# GG-CC1101_v1.net
KiCad netlist of a schematic drawn in EAGLE
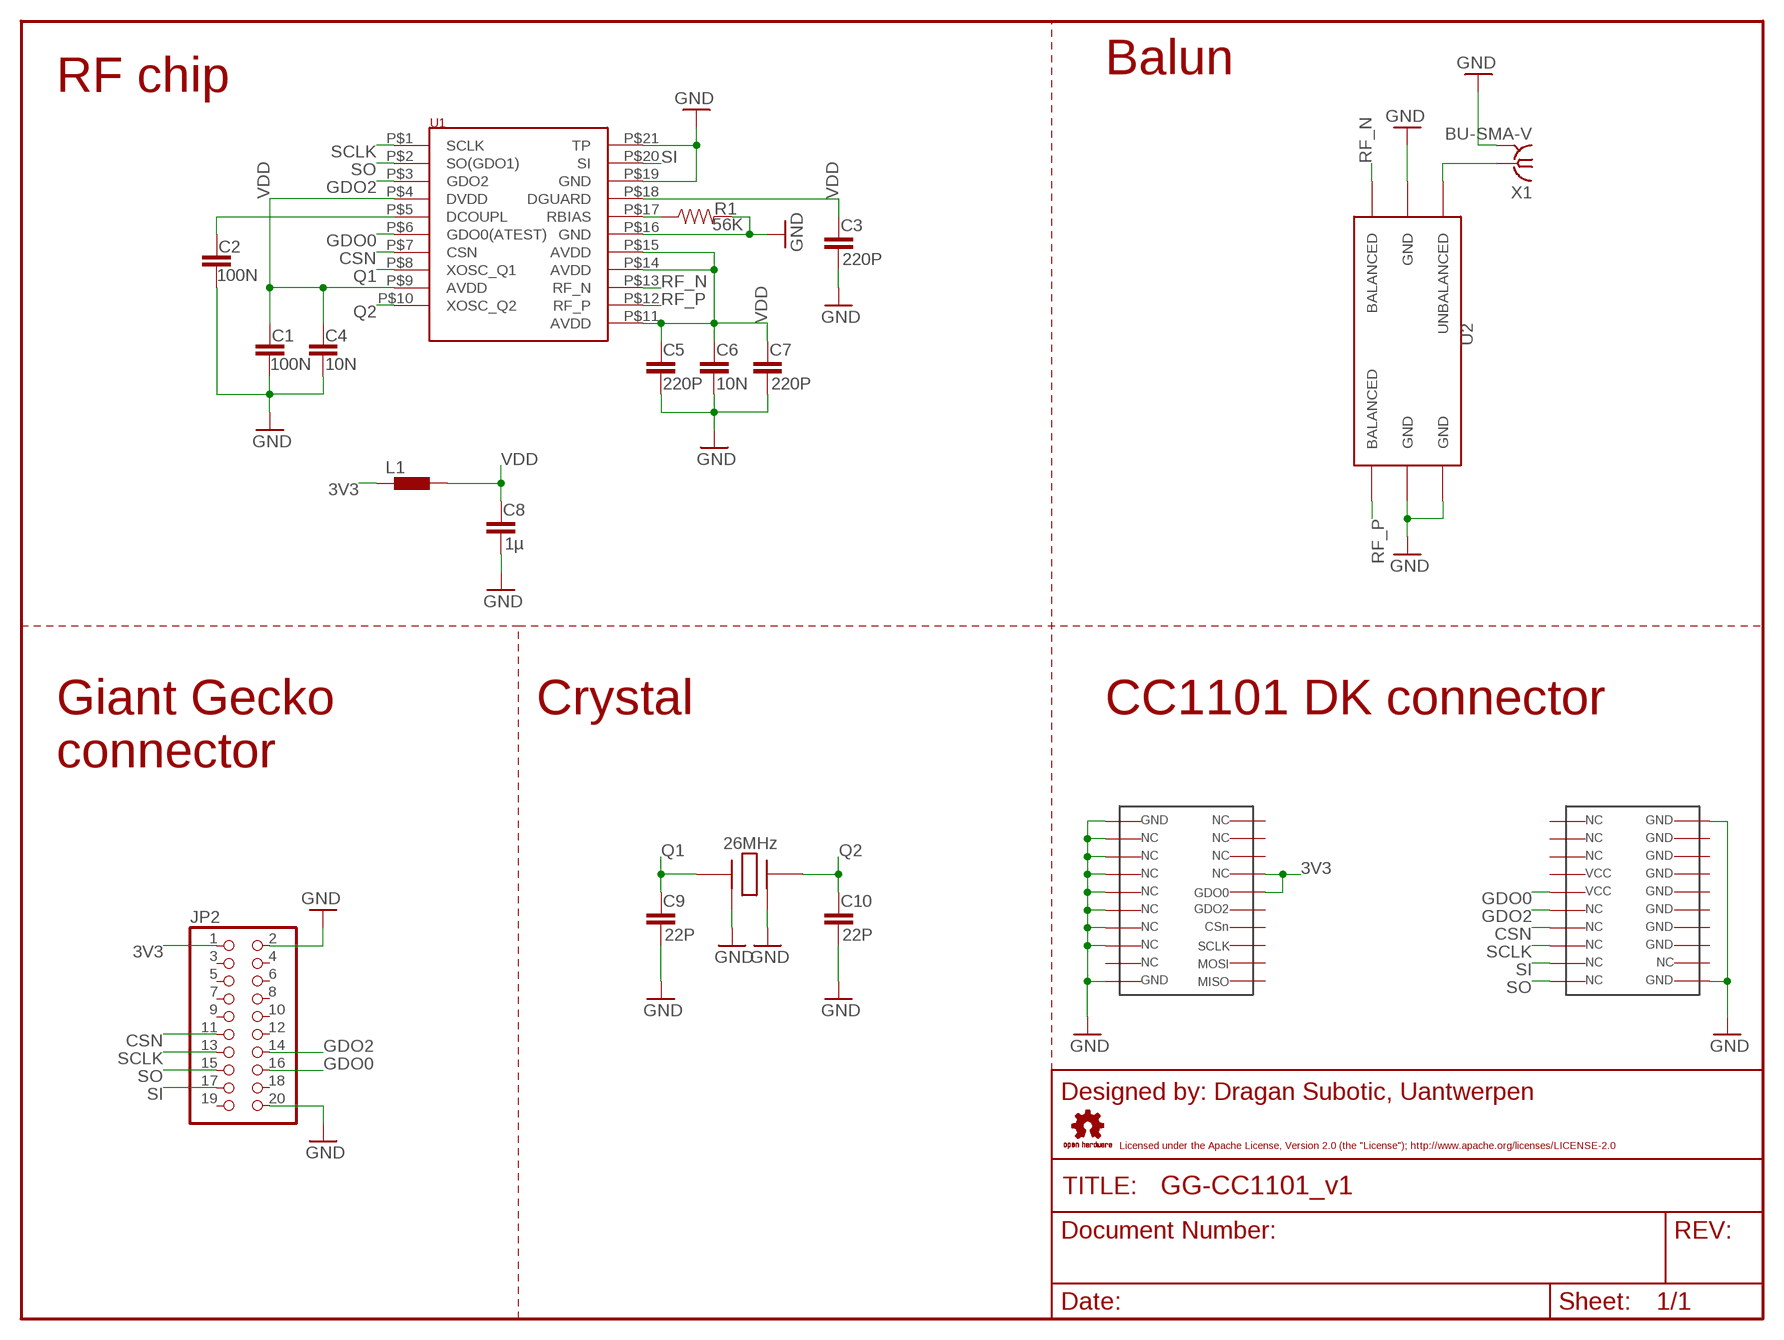
[diagram p0: schematic, sheet 1]

(export (version "E")
  (design (tool "Eeschema 10.0.6"))
  (components
    (comp (ref "C1")
      (value "100N")
      (footprint "eagle-import:0805")
      (libsource (lib "eagle-import") (part "CAP0805"))
    )
    (comp (ref "C2")
      (value "100N")
      (footprint "eagle-import:0805")
      (libsource (lib "eagle-import") (part "CAP0805"))
    )
    (comp (ref "C3")
      (value "220P")
      (footprint "eagle-import:0805")
      (libsource (lib "eagle-import") (part "CAP0805"))
    )
    (comp (ref "C4")
      (value "10N")
      (footprint "eagle-import:0805")
      (libsource (lib "eagle-import") (part "CAP0805"))
    )
    (comp (ref "C5")
      (value "220P")
      (footprint "eagle-import:0805")
      (libsource (lib "eagle-import") (part "CAP0805"))
    )
    (comp (ref "C6")
      (value "10N")
      (footprint "eagle-import:0805")
      (libsource (lib "eagle-import") (part "CAP0805"))
    )
    (comp (ref "C7")
      (value "220P")
      (footprint "eagle-import:0805")
      (libsource (lib "eagle-import") (part "CAP0805"))
    )
    (comp (ref "C8")
      (value "1µ")
      (footprint "eagle-import:0805")
      (libsource (lib "eagle-import") (part "CAP0805"))
    )
    (comp (ref "C9")
      (value "22P")
      (footprint "eagle-import:0805")
      (libsource (lib "eagle-import") (part "CAP0805"))
    )
    (comp (ref "C10")
      (value "22P")
      (footprint "eagle-import:0805")
      (libsource (lib "eagle-import") (part "CAP0805"))
    )
    (comp (ref "JP2")
      (value "PINHD-2X10")
      (footprint "eagle-import:2X10")
      (libsource (lib "eagle-import") (part "PINHD-2X10"))
    )
    (comp (ref "L1")
      (value "BLM15HG102SN1")
      (footprint "eagle-import:0402")
      (libsource (lib "eagle-import") (part "BLM15HG102SN1"))
    )
    (comp (ref "R1")
      (value "56K")
      (footprint "eagle-import:0805")
      (libsource (lib "eagle-import") (part "RESISTOR0805-RES"))
    )
    (comp (ref "U$1")
      (value "CC1101-EVAL_KIT")
      (footprint "eagle-import:CC1101-EVAL_KIT")
      (libsource (lib "eagle-import") (part "CC1101-EVAL_KIT"))
    )
    (comp (ref "U$2")
      (value "XTAL-26MHZ")
      (footprint "eagle-import:XTAL-26MHZ")
      (libsource (lib "eagle-import") (part "XTAL-26MHZ"))
    )
    (comp (ref "U1")
      (value "CC1101")
      (footprint "eagle-import:CC1101")
      (libsource (lib "eagle-import") (part "CC1101"))
    )
    (comp (ref "U2")
      (value "BALUN-433MHZ")
      (footprint "eagle-import:BALUN-433MHZ")
      (libsource (lib "eagle-import") (part "BALUN-433MHZ"))
    )
    (comp (ref "X1")
      (value "BU-SMA-V")
      (footprint "eagle-import:BU-SMA-V")
      (libsource (lib "eagle-import") (part "BU-SMA-V"))
    )
  )
  (nets
    (net (code "1") (name "/3V3") (class "Default")
      (node (ref "JP2") (pin "1") (pinfunction "1_1") (pintype "passive"))
      (node (ref "L1") (pin "1") (pinfunction "1_1") (pintype "passive"))
      (node (ref "U$1") (pin "P$14") (pinfunction "P$14_P$14") (pintype "bidirectional"))
      (node (ref "U$1") (pin "P$15") (pinfunction "P$15_P$15") (pintype "bidirectional"))
    )
    (net (code "2") (name "/CSN") (class "Default")
      (node (ref "JP2") (pin "11") (pinfunction "11_11") (pintype "passive"))
      (node (ref "U$1") (pin "P$24") (pinfunction "P$24_P$24") (pintype "bidirectional"))
      (node (ref "U1") (pin "P$7") (pinfunction "CSN_P$7") (pintype "bidirectional"))
    )
    (net (code "3") (name "/GDO0") (class "Default")
      (node (ref "JP2") (pin "16") (pinfunction "16_16") (pintype "passive"))
      (node (ref "U$1") (pin "P$26") (pinfunction "P$26_P$26") (pintype "bidirectional"))
      (node (ref "U1") (pin "P$6") (pinfunction "GDO0(ATEST)_P$6") (pintype "bidirectional"))
    )
    (net (code "4") (name "/GDO2") (class "Default")
      (node (ref "JP2") (pin "14") (pinfunction "14_14") (pintype "passive"))
      (node (ref "U$1") (pin "P$25") (pinfunction "P$25_P$25") (pintype "bidirectional"))
      (node (ref "U1") (pin "P$3") (pinfunction "GDO2_P$3") (pintype "bidirectional"))
    )
    (net (code "5") (name "/Q1") (class "Default")
      (node (ref "C9") (pin "1") (pinfunction "1_1") (pintype "passive"))
      (node (ref "U$2") (pin "P$1") (pinfunction "P$1_P$1") (pintype "bidirectional"))
      (node (ref "U1") (pin "P$8") (pinfunction "XOSC_Q1_P$8") (pintype "bidirectional"))
    )
    (net (code "6") (name "/Q2") (class "Default")
      (node (ref "C10") (pin "1") (pinfunction "1_1") (pintype "passive"))
      (node (ref "U$2") (pin "P$3") (pinfunction "P$3_P$3") (pintype "bidirectional"))
      (node (ref "U1") (pin "P$10") (pinfunction "XOSC_Q2_P$10") (pintype "bidirectional"))
    )
    (net (code "7") (name "/RF_N") (class "Default")
      (node (ref "U1") (pin "P$13") (pinfunction "RF_N_P$13") (pintype "bidirectional"))
      (node (ref "U2") (pin "P$3") (pinfunction "BALANCED_P$3") (pintype "bidirectional"))
    )
    (net (code "8") (name "/RF_P") (class "Default")
      (node (ref "U1") (pin "P$12") (pinfunction "RF_P_P$12") (pintype "bidirectional"))
      (node (ref "U2") (pin "P$4") (pinfunction "BALANCED_P$4") (pintype "bidirectional"))
    )
    (net (code "9") (name "/SCLK") (class "Default")
      (node (ref "JP2") (pin "13") (pinfunction "13_13") (pintype "passive"))
      (node (ref "U$1") (pin "P$23") (pinfunction "P$23_P$23") (pintype "bidirectional"))
      (node (ref "U1") (pin "P$1") (pinfunction "SCLK_P$1") (pintype "bidirectional"))
    )
    (net (code "10") (name "/SI") (class "Default")
      (node (ref "JP2") (pin "17") (pinfunction "17_17") (pintype "passive"))
      (node (ref "U$1") (pin "P$22") (pinfunction "P$22_P$22") (pintype "bidirectional"))
      (node (ref "U1") (pin "P$20") (pinfunction "SI_P$20") (pintype "bidirectional"))
    )
    (net (code "11") (name "/SO") (class "Default")
      (node (ref "JP2") (pin "15") (pinfunction "15_15") (pintype "passive"))
      (node (ref "U$1") (pin "P$21") (pinfunction "P$21_P$21") (pintype "bidirectional"))
      (node (ref "U1") (pin "P$2") (pinfunction "SO(GDO1)_P$2") (pintype "bidirectional"))
    )
    (net (code "12") (name "/VDD") (class "Default")
      (node (ref "C1") (pin "1") (pinfunction "1_1") (pintype "passive"))
      (node (ref "C3") (pin "1") (pinfunction "1_1") (pintype "passive"))
      (node (ref "C4") (pin "1") (pinfunction "1_1") (pintype "passive"))
      (node (ref "C5") (pin "1") (pinfunction "1_1") (pintype "passive"))
      (node (ref "C6") (pin "1") (pinfunction "1_1") (pintype "passive"))
      (node (ref "C7") (pin "1") (pinfunction "1_1") (pintype "passive"))
      (node (ref "C8") (pin "1") (pinfunction "1_1") (pintype "passive"))
      (node (ref "L1") (pin "2") (pinfunction "2_2") (pintype "passive"))
      (node (ref "U1") (pin "P$11") (pinfunction "AVDD_P$11") (pintype "bidirectional"))
      (node (ref "U1") (pin "P$14") (pinfunction "AVDD_P$14") (pintype "bidirectional"))
      (node (ref "U1") (pin "P$15") (pinfunction "AVDD_P$15") (pintype "bidirectional"))
      (node (ref "U1") (pin "P$18") (pinfunction "DGUARD_P$18") (pintype "bidirectional"))
      (node (ref "U1") (pin "P$4") (pinfunction "DVDD_P$4") (pintype "bidirectional"))
      (node (ref "U1") (pin "P$9") (pinfunction "AVDD_P$9") (pintype "bidirectional"))
    )
    (net (code "13") (name "GND") (class "Default")
      (node (ref "C1") (pin "2") (pinfunction "2_2") (pintype "passive"))
      (node (ref "C10") (pin "2") (pinfunction "2_2") (pintype "passive"))
      (node (ref "C2") (pin "2") (pinfunction "2_2") (pintype "passive"))
      (node (ref "C3") (pin "2") (pinfunction "2_2") (pintype "passive"))
      (node (ref "C4") (pin "2") (pinfunction "2_2") (pintype "passive"))
      (node (ref "C5") (pin "2") (pinfunction "2_2") (pintype "passive"))
      (node (ref "C6") (pin "2") (pinfunction "2_2") (pintype "passive"))
      (node (ref "C7") (pin "2") (pinfunction "2_2") (pintype "passive"))
      (node (ref "C8") (pin "2") (pinfunction "2_2") (pintype "passive"))
      (node (ref "C9") (pin "2") (pinfunction "2_2") (pintype "passive"))
      (node (ref "JP2") (pin "2") (pinfunction "2_2") (pintype "passive"))
      (node (ref "JP2") (pin "20") (pinfunction "20_20") (pintype "passive"))
      (node (ref "R1") (pin "2") (pinfunction "2_2") (pintype "passive"))
      (node (ref "U$1") (pin "P$1") (pinfunction "P$1_P$1") (pintype "bidirectional"))
      (node (ref "U$1") (pin "P$10") (pinfunction "P$10_P$10") (pintype "bidirectional"))
      (node (ref "U$1") (pin "P$3") (pinfunction "P$3_P$3") (pintype "bidirectional"))
      (node (ref "U$1") (pin "P$31") (pinfunction "P$31_P$31") (pintype "bidirectional"))
      (node (ref "U$1") (pin "P$4") (pinfunction "P$4_P$4") (pintype "bidirectional"))
      (node (ref "U$1") (pin "P$40") (pinfunction "P$40_P$40") (pintype "bidirectional"))
      (node (ref "U$1") (pin "P$5") (pinfunction "P$5_P$5") (pintype "bidirectional"))
      (node (ref "U$1") (pin "P$6") (pinfunction "P$6_P$6") (pintype "bidirectional"))
      (node (ref "U$1") (pin "P$7") (pinfunction "P$7_P$7") (pintype "bidirectional"))
      (node (ref "U$1") (pin "P$8") (pinfunction "P$8_P$8") (pintype "bidirectional"))
      (node (ref "U$1") (pin "P$9") (pinfunction "P$9_P$9") (pintype "bidirectional"))
      (node (ref "U$2") (pin "P$2") (pinfunction "P$2_P$2") (pintype "bidirectional"))
      (node (ref "U$2") (pin "P$4") (pinfunction "P$4_P$4") (pintype "bidirectional"))
      (node (ref "U1") (pin "P$16") (pinfunction "GND_P$16") (pintype "bidirectional"))
      (node (ref "U1") (pin "P$19") (pinfunction "GND_P$19") (pintype "bidirectional"))
      (node (ref "U1") (pin "P$21") (pinfunction "TP_P$21") (pintype "bidirectional"))
      (node (ref "U2") (pin "P$2") (pinfunction "GND_P$2") (pintype "bidirectional"))
      (node (ref "U2") (pin "P$5") (pinfunction "GND_P$5") (pintype "bidirectional"))
      (node (ref "U2") (pin "P$6") (pinfunction "GND_P$6") (pintype "bidirectional"))
      (node (ref "X1") (pin "2") (pinfunction "2_2") (pintype "passive"))
      (node (ref "X1") (pin "3") (pinfunction "2_3") (pintype "passive"))
      (node (ref "X1") (pin "4") (pinfunction "2_4") (pintype "passive"))
      (node (ref "X1") (pin "5") (pinfunction "2_5") (pintype "passive"))
    )
    (net (code "14") (name "Net-(U1-DCOUPL)") (class "Default")
      (node (ref "C2") (pin "1") (pinfunction "1_1") (pintype "passive"))
      (node (ref "U1") (pin "P$5") (pinfunction "DCOUPL_P$5") (pintype "bidirectional"))
    )
    (net (code "15") (name "Net-(U1-RBIAS)") (class "Default")
      (node (ref "R1") (pin "1") (pinfunction "1_1") (pintype "passive"))
      (node (ref "U1") (pin "P$17") (pinfunction "RBIAS_P$17") (pintype "bidirectional"))
    )
    (net (code "16") (name "Net-(U2-UNBALANCED)") (class "Default")
      (node (ref "U2") (pin "P$1") (pinfunction "UNBALANCED_P$1") (pintype "bidirectional"))
      (node (ref "X1") (pin "1") (pinfunction "1_1") (pintype "passive"))
    )
    (net (code "17") (name "unconnected-(JP2-Pad3)") (class "Default")
      (node (ref "JP2") (pin "3") (pinfunction "3_3") (pintype "passive"))
    )
    (net (code "18") (name "unconnected-(JP2-Pad4)") (class "Default")
      (node (ref "JP2") (pin "4") (pinfunction "4_4") (pintype "passive"))
    )
    (net (code "19") (name "unconnected-(JP2-Pad5)") (class "Default")
      (node (ref "JP2") (pin "5") (pinfunction "5_5") (pintype "passive"))
    )
    (net (code "20") (name "unconnected-(JP2-Pad6)") (class "Default")
      (node (ref "JP2") (pin "6") (pinfunction "6_6") (pintype "passive"))
    )
    (net (code "21") (name "unconnected-(JP2-Pad7)") (class "Default")
      (node (ref "JP2") (pin "7") (pinfunction "7_7") (pintype "passive"))
    )
    (net (code "22") (name "unconnected-(JP2-Pad8)") (class "Default")
      (node (ref "JP2") (pin "8") (pinfunction "8_8") (pintype "passive"))
    )
    (net (code "23") (name "unconnected-(JP2-Pad9)") (class "Default")
      (node (ref "JP2") (pin "9") (pinfunction "9_9") (pintype "passive"))
    )
    (net (code "24") (name "unconnected-(JP2-Pad10)") (class "Default")
      (node (ref "JP2") (pin "10") (pinfunction "10_10") (pintype "passive"))
    )
    (net (code "25") (name "unconnected-(JP2-Pad12)") (class "Default")
      (node (ref "JP2") (pin "12") (pinfunction "12_12") (pintype "passive"))
    )
    (net (code "26") (name "unconnected-(JP2-Pad18)") (class "Default")
      (node (ref "JP2") (pin "18") (pinfunction "18_18") (pintype "passive"))
    )
    (net (code "27") (name "unconnected-(JP2-Pad19)") (class "Default")
      (node (ref "JP2") (pin "19") (pinfunction "19_19") (pintype "passive"))
    )
    (net (code "28") (name "unconnected-(U$1-PadP$2)") (class "Default")
      (node (ref "U$1") (pin "P$2") (pinfunction "P$2_P$2") (pintype "bidirectional"))
    )
    (net (code "29") (name "unconnected-(U$1-PadP$11)") (class "Default")
      (node (ref "U$1") (pin "P$11") (pinfunction "P$11_P$11") (pintype "bidirectional"))
    )
    (net (code "30") (name "unconnected-(U$1-PadP$12)") (class "Default")
      (node (ref "U$1") (pin "P$12") (pinfunction "P$12_P$12") (pintype "bidirectional"))
    )
    (net (code "31") (name "unconnected-(U$1-PadP$13)") (class "Default")
      (node (ref "U$1") (pin "P$13") (pinfunction "P$13_P$13") (pintype "bidirectional"))
    )
    (net (code "32") (name "unconnected-(U$1-PadP$16)") (class "Default")
      (node (ref "U$1") (pin "P$16") (pinfunction "P$16_P$16") (pintype "bidirectional"))
    )
    (net (code "33") (name "unconnected-(U$1-PadP$17)") (class "Default")
      (node (ref "U$1") (pin "P$17") (pinfunction "P$17_P$17") (pintype "bidirectional"))
    )
    (net (code "34") (name "unconnected-(U$1-PadP$18)") (class "Default")
      (node (ref "U$1") (pin "P$18") (pinfunction "P$18_P$18") (pintype "bidirectional"))
    )
    (net (code "35") (name "unconnected-(U$1-PadP$19)") (class "Default")
      (node (ref "U$1") (pin "P$19") (pinfunction "P$19_P$19") (pintype "bidirectional"))
    )
    (net (code "36") (name "unconnected-(U$1-PadP$20)") (class "Default")
      (node (ref "U$1") (pin "P$20") (pinfunction "P$20_P$20") (pintype "bidirectional"))
    )
    (net (code "37") (name "unconnected-(U$1-PadP$27)") (class "Default")
      (node (ref "U$1") (pin "P$27") (pinfunction "P$27_P$27") (pintype "bidirectional"))
    )
    (net (code "38") (name "unconnected-(U$1-PadP$28)") (class "Default")
      (node (ref "U$1") (pin "P$28") (pinfunction "P$28_P$28") (pintype "bidirectional"))
    )
    (net (code "39") (name "unconnected-(U$1-PadP$29)") (class "Default")
      (node (ref "U$1") (pin "P$29") (pinfunction "P$29_P$29") (pintype "bidirectional"))
    )
    (net (code "40") (name "unconnected-(U$1-PadP$30)") (class "Default")
      (node (ref "U$1") (pin "P$30") (pinfunction "P$30_P$30") (pintype "bidirectional"))
    )
    (net (code "41") (name "unconnected-(U$1-PadP$32)") (class "Default")
      (node (ref "U$1") (pin "P$32") (pinfunction "P$32_P$32") (pintype "bidirectional"))
    )
    (net (code "42") (name "unconnected-(U$1-PadP$33)") (class "Default")
      (node (ref "U$1") (pin "P$33") (pinfunction "P$33_P$33") (pintype "bidirectional"))
    )
    (net (code "43") (name "unconnected-(U$1-PadP$34)") (class "Default")
      (node (ref "U$1") (pin "P$34") (pinfunction "P$34_P$34") (pintype "bidirectional"))
    )
    (net (code "44") (name "unconnected-(U$1-PadP$35)") (class "Default")
      (node (ref "U$1") (pin "P$35") (pinfunction "P$35_P$35") (pintype "bidirectional"))
    )
    (net (code "45") (name "unconnected-(U$1-PadP$36)") (class "Default")
      (node (ref "U$1") (pin "P$36") (pinfunction "P$36_P$36") (pintype "bidirectional"))
    )
    (net (code "46") (name "unconnected-(U$1-PadP$37)") (class "Default")
      (node (ref "U$1") (pin "P$37") (pinfunction "P$37_P$37") (pintype "bidirectional"))
    )
    (net (code "47") (name "unconnected-(U$1-PadP$38)") (class "Default")
      (node (ref "U$1") (pin "P$38") (pinfunction "P$38_P$38") (pintype "bidirectional"))
    )
    (net (code "48") (name "unconnected-(U$1-PadP$39)") (class "Default")
      (node (ref "U$1") (pin "P$39") (pinfunction "P$39_P$39") (pintype "bidirectional"))
    )
  )
)
